# switch.net
KiCad netlist of a schematic drawn in EAGLE
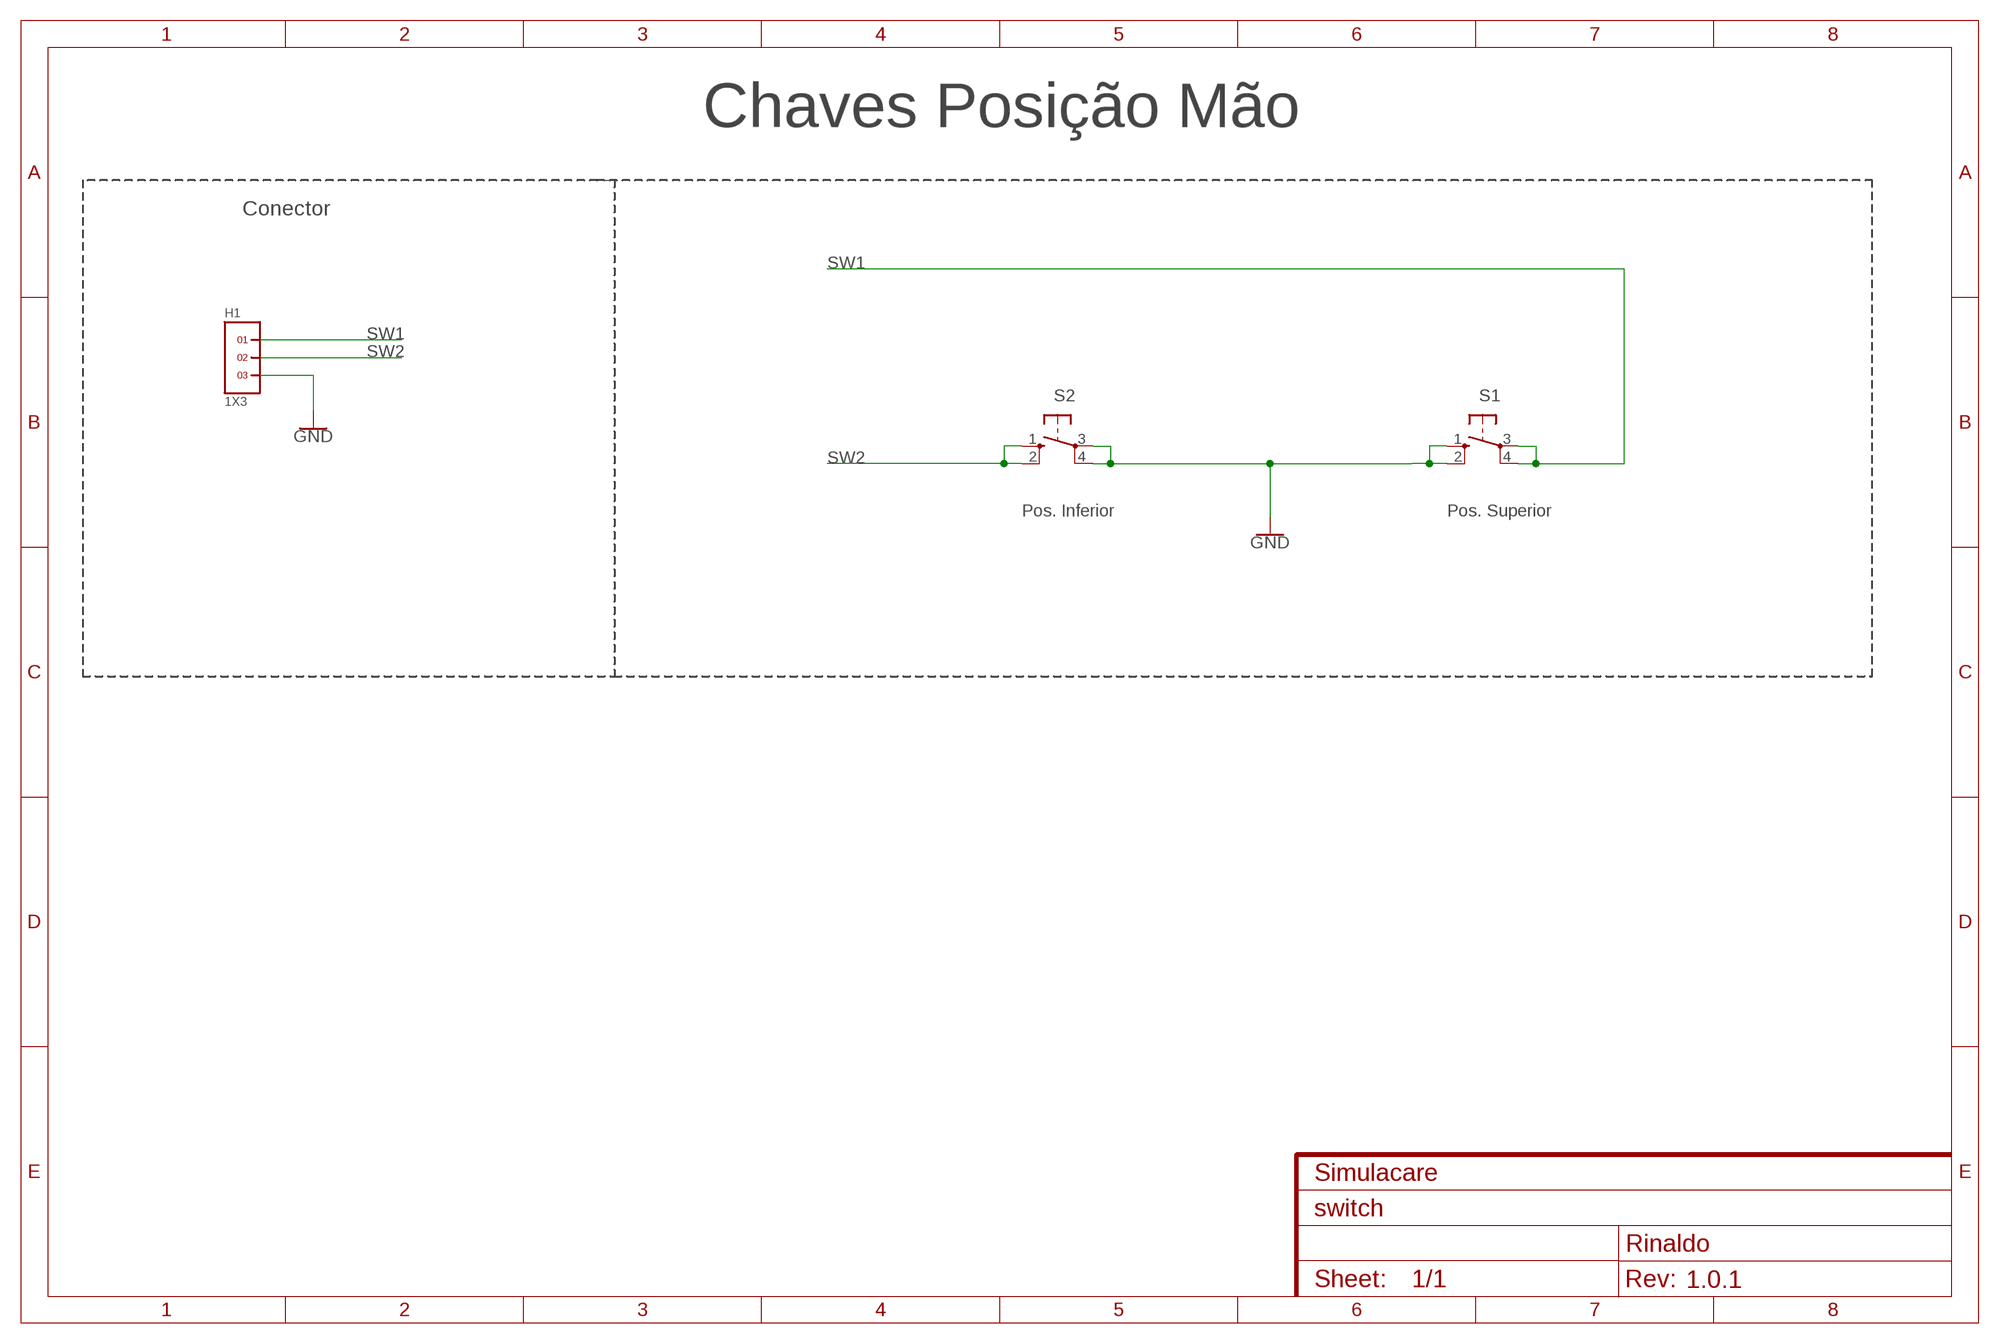
[diagram p0: schematic, sheet 1]

(export (version "E")
  (design (tool "Eeschema 10.0.6"))
  (components
    (comp (ref "H1")
      (value "1X3")
      (footprint "eagle-import:1X3")
      (libsource (lib "eagle-import") (part "1X3"))
    )
    (comp (ref "S1")
      (value "40-XX")
      (footprint "eagle-import:B3F-40XX")
      (fields (field (name "MF") "OMRON COMPONENTS USA") (field (name "MPN") "B3F-4000"))
      (libsource (lib "eagle-import") (part "40-XX"))
    )
    (comp (ref "S2")
      (value "40-XX")
      (footprint "eagle-import:B3F-40XX")
      (fields (field (name "MF") "OMRON COMPONENTS USA") (field (name "MPN") "B3F-4000"))
      (libsource (lib "eagle-import") (part "40-XX"))
    )
  )
  (nets
    (net (code "1") (name "/SW1") (class "Default")
      (node (ref "H1") (pin "1") (pinfunction "1_1") (pintype "bidirectional"))
      (node (ref "S1") (pin "3") (pinfunction "P_3") (pintype "passive"))
      (node (ref "S1") (pin "4") (pinfunction "P1_4") (pintype "passive"))
    )
    (net (code "2") (name "/SW2") (class "Default")
      (node (ref "H1") (pin "2") (pinfunction "2_2") (pintype "bidirectional"))
      (node (ref "S2") (pin "1") (pinfunction "S_1") (pintype "passive"))
      (node (ref "S2") (pin "2") (pinfunction "S1_2") (pintype "passive"))
    )
    (net (code "3") (name "GND") (class "Default")
      (node (ref "H1") (pin "3") (pinfunction "3_3") (pintype "bidirectional"))
      (node (ref "S1") (pin "1") (pinfunction "S_1") (pintype "passive"))
      (node (ref "S1") (pin "2") (pinfunction "S1_2") (pintype "passive"))
      (node (ref "S2") (pin "3") (pinfunction "P_3") (pintype "passive"))
      (node (ref "S2") (pin "4") (pinfunction "P1_4") (pintype "passive"))
    )
  )
)
